# encoder.net
KiCad netlist of a schematic drawn in Altium Designer
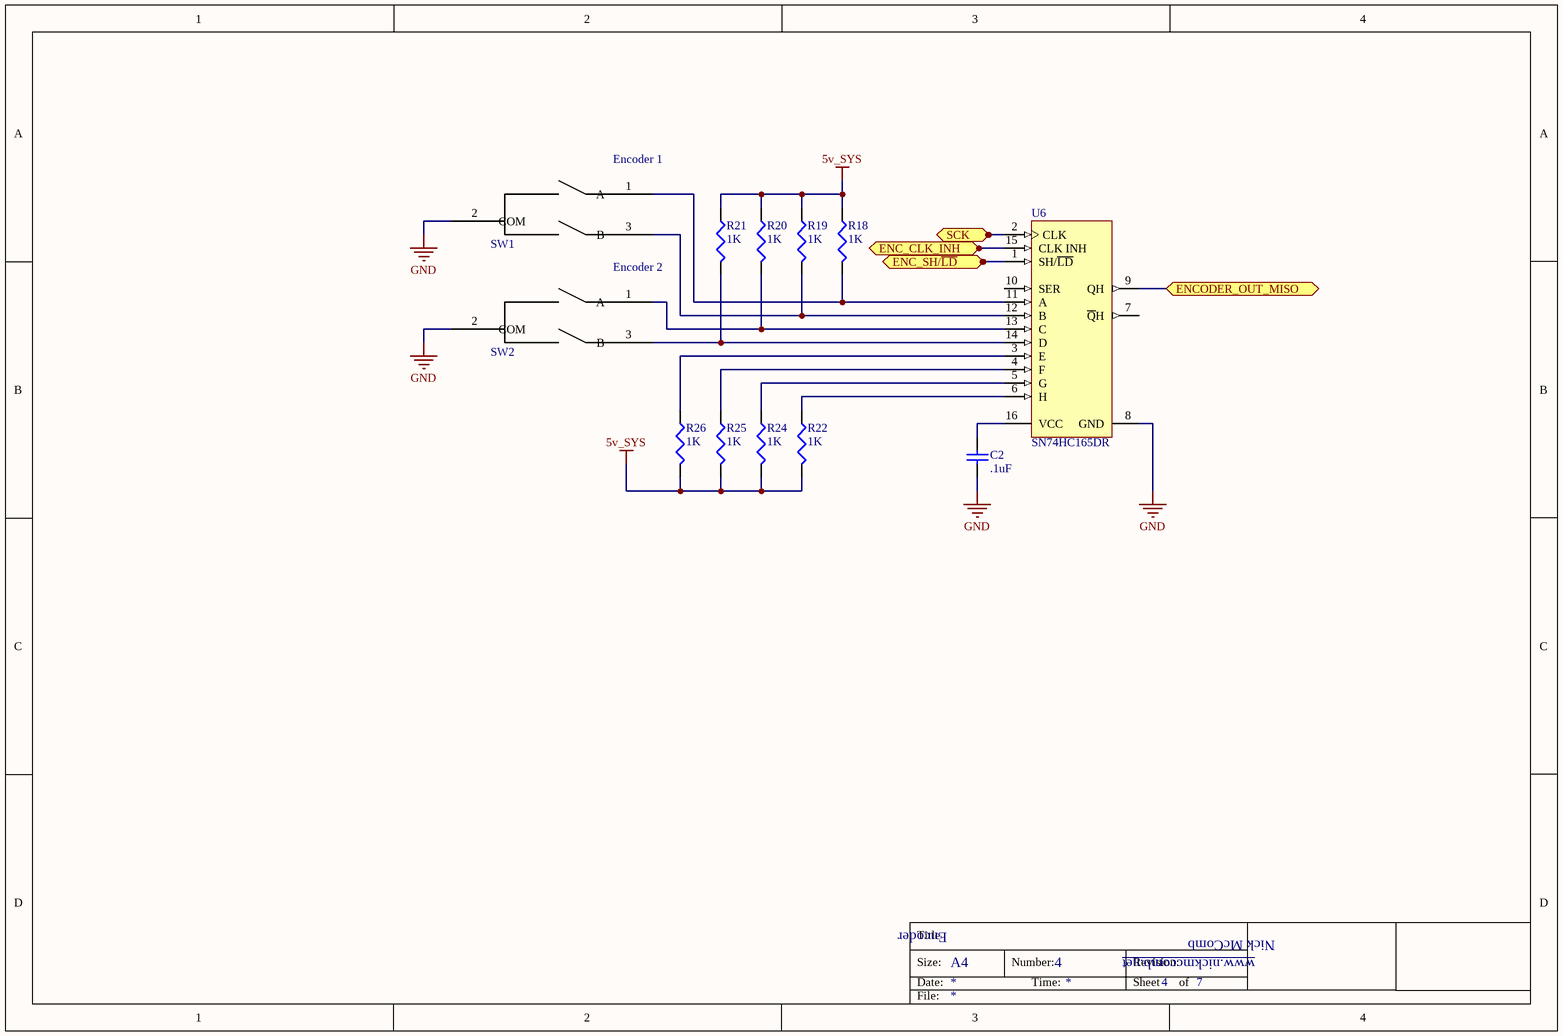
[diagram p0: encoder.SchDoc]

(export (version "E")
  (design (tool "Eeschema 10.0.6"))
  (components
    (comp (ref "C2")
      (value ".1uF")
      (footprint "C0805")
      (description "Capacitor")
      (fields (field (name "Comment") "0805 style, by default") (field (name "PUBLISHER") "Altium Limited"))
      (libsource (lib "lab2") (part "Cap"))
    )
    (comp (ref "R18")
      (value "1K")
      (footprint "J1-0603")
      (description "Resistor")
      (fields (field (name "PUBLISHER") "Altium Limited"))
      (libsource (lib "lab2") (part "Res3"))
    )
    (comp (ref "R19")
      (value "1K")
      (footprint "J1-0603")
      (description "Resistor")
      (fields (field (name "PUBLISHER") "Altium Limited"))
      (libsource (lib "lab2") (part "Res3"))
    )
    (comp (ref "R20")
      (value "1K")
      (footprint "J1-0603")
      (description "Resistor")
      (fields (field (name "PUBLISHER") "Altium Limited"))
      (libsource (lib "lab2") (part "Res3"))
    )
    (comp (ref "R21")
      (value "1K")
      (footprint "J1-0603")
      (description "Resistor")
      (fields (field (name "PUBLISHER") "Altium Limited"))
      (libsource (lib "lab2") (part "Res3"))
    )
    (comp (ref "R22")
      (value "1K")
      (footprint "J1-0603")
      (description "Resistor")
      (fields (field (name "PUBLISHER") "Altium Limited"))
      (libsource (lib "lab2") (part "Res3"))
    )
    (comp (ref "R24")
      (value "1K")
      (footprint "J1-0603")
      (description "Resistor")
      (fields (field (name "PUBLISHER") "Altium Limited"))
      (libsource (lib "lab2") (part "Res3"))
    )
    (comp (ref "R25")
      (value "1K")
      (footprint "J1-0603")
      (description "Resistor")
      (fields (field (name "PUBLISHER") "Altium Limited"))
      (libsource (lib "lab2") (part "Res3"))
    )
    (comp (ref "R26")
      (value "1K")
      (footprint "J1-0603")
      (description "Resistor")
      (fields (field (name "PUBLISHER") "Altium Limited"))
      (libsource (lib "lab2") (part "Res3"))
    )
    (comp (ref "SW1") (value "ENCODER") (footprint "ENCODER") (libsource (lib "lab2") (part "ENCODER")))
    (comp (ref "SW2") (value "ENCODER") (footprint "ENCODER") (libsource (lib "lab2") (part "ENCODER")))
    (comp (ref "U6")
      (value "SN74HC165DR")
      (footprint "D0016A_L")
      (description "8-Bit Parallel-Load Shift Registers, D0016A, LARGE T&R")
      (fields (field (name "PART NUMBER") "SN74HC165"))
      (libsource (lib "Altium Content Vault") (part "TI-SNX4XXX165X-16"))
    )
  )
  (nets
    (net (code "1") (name "/ENCODER_OUT_MISO") (class "Default")
      (node (ref "U6") (pin "9") (pinfunction "QH_9") (pintype "output"))
    )
    (net (code "2") (name "/ENC_CLK_INH") (class "Default")
      (node (ref "U6") (pin "15") (pinfunction "CLK_INH_15") (pintype "input"))
    )
    (net (code "3") (name "/ENC_SH{slash}~{LD}") (class "Default")
      (node (ref "U6") (pin "1") (pinfunction "SH/~{LD}_1") (pintype "input"))
    )
    (net (code "4") (name "/SCK") (class "Default")
      (node (ref "U6") (pin "2") (pinfunction "CLK_2") (pintype "input"))
    )
    (net (code "5") (name "5v_SYS") (class "Default")
      (node (ref "R18") (pin "2") (pinfunction "2_2") (pintype "passive"))
      (node (ref "R19") (pin "2") (pinfunction "2_2") (pintype "passive"))
      (node (ref "R20") (pin "2") (pinfunction "2_2") (pintype "passive"))
      (node (ref "R21") (pin "2") (pinfunction "2_2") (pintype "passive"))
      (node (ref "R22") (pin "1") (pinfunction "1_1") (pintype "passive"))
      (node (ref "R24") (pin "1") (pinfunction "1_1") (pintype "passive"))
      (node (ref "R25") (pin "1") (pinfunction "1_1") (pintype "passive"))
      (node (ref "R26") (pin "1") (pinfunction "1_1") (pintype "passive"))
    )
    (net (code "6") (name "GND") (class "Default")
      (node (ref "C2") (pin "1") (pinfunction "1_1") (pintype "passive"))
      (node (ref "SW1") (pin "2") (pinfunction "COM_2") (pintype "passive"))
      (node (ref "SW2") (pin "2") (pinfunction "COM_2") (pintype "passive"))
      (node (ref "U6") (pin "8") (pinfunction "GND_8") (pintype "power_in"))
    )
    (net (code "7") (name "Net-(SW1-A)") (class "Default")
      (node (ref "R18") (pin "1") (pinfunction "1_1") (pintype "passive"))
      (node (ref "SW1") (pin "1") (pinfunction "A_1") (pintype "passive"))
      (node (ref "U6") (pin "11") (pinfunction "A_11") (pintype "input"))
    )
    (net (code "8") (name "Net-(SW1-B)") (class "Default")
      (node (ref "R19") (pin "1") (pinfunction "1_1") (pintype "passive"))
      (node (ref "SW1") (pin "3") (pinfunction "B_3") (pintype "passive"))
      (node (ref "U6") (pin "12") (pinfunction "B_12") (pintype "input"))
    )
    (net (code "9") (name "Net-(SW2-A)") (class "Default")
      (node (ref "R20") (pin "1") (pinfunction "1_1") (pintype "passive"))
      (node (ref "SW2") (pin "1") (pinfunction "A_1") (pintype "passive"))
      (node (ref "U6") (pin "13") (pinfunction "C_13") (pintype "input"))
    )
    (net (code "10") (name "Net-(SW2-B)") (class "Default")
      (node (ref "R21") (pin "1") (pinfunction "1_1") (pintype "passive"))
      (node (ref "SW2") (pin "3") (pinfunction "B_3") (pintype "passive"))
      (node (ref "U6") (pin "14") (pinfunction "D_14") (pintype "input"))
    )
    (net (code "11") (name "Net-(U6-E)") (class "Default")
      (node (ref "R26") (pin "2") (pinfunction "2_2") (pintype "passive"))
      (node (ref "U6") (pin "3") (pinfunction "E_3") (pintype "input"))
    )
    (net (code "12") (name "Net-(U6-F)") (class "Default")
      (node (ref "R25") (pin "2") (pinfunction "2_2") (pintype "passive"))
      (node (ref "U6") (pin "4") (pinfunction "F_4") (pintype "input"))
    )
    (net (code "13") (name "Net-(U6-G)") (class "Default")
      (node (ref "R24") (pin "2") (pinfunction "2_2") (pintype "passive"))
      (node (ref "U6") (pin "5") (pinfunction "G_5") (pintype "input"))
    )
    (net (code "14") (name "Net-(U6-H)") (class "Default")
      (node (ref "R22") (pin "2") (pinfunction "2_2") (pintype "passive"))
      (node (ref "U6") (pin "6") (pinfunction "H_6") (pintype "input"))
    )
    (net (code "15") (name "Net-(U6-VCC)") (class "Default")
      (node (ref "C2") (pin "2") (pinfunction "2_2") (pintype "passive"))
      (node (ref "U6") (pin "16") (pinfunction "VCC_16") (pintype "power_in"))
    )
    (net (code "16") (name "unconnected-(U6-SER-Pad10)") (class "Default")
      (node (ref "U6") (pin "10") (pinfunction "SER_10") (pintype "input"))
    )
    (net (code "17") (name "unconnected-(U6-~{Q}H-Pad7)") (class "Default")
      (node (ref "U6") (pin "7") (pinfunction "~{Q}H_7") (pintype "output"))
    )
  )
)
